# MCB-USI-WM-BN-BM-22-v1_0_0.net
KiCad netlist of a schematic drawn in EAGLE
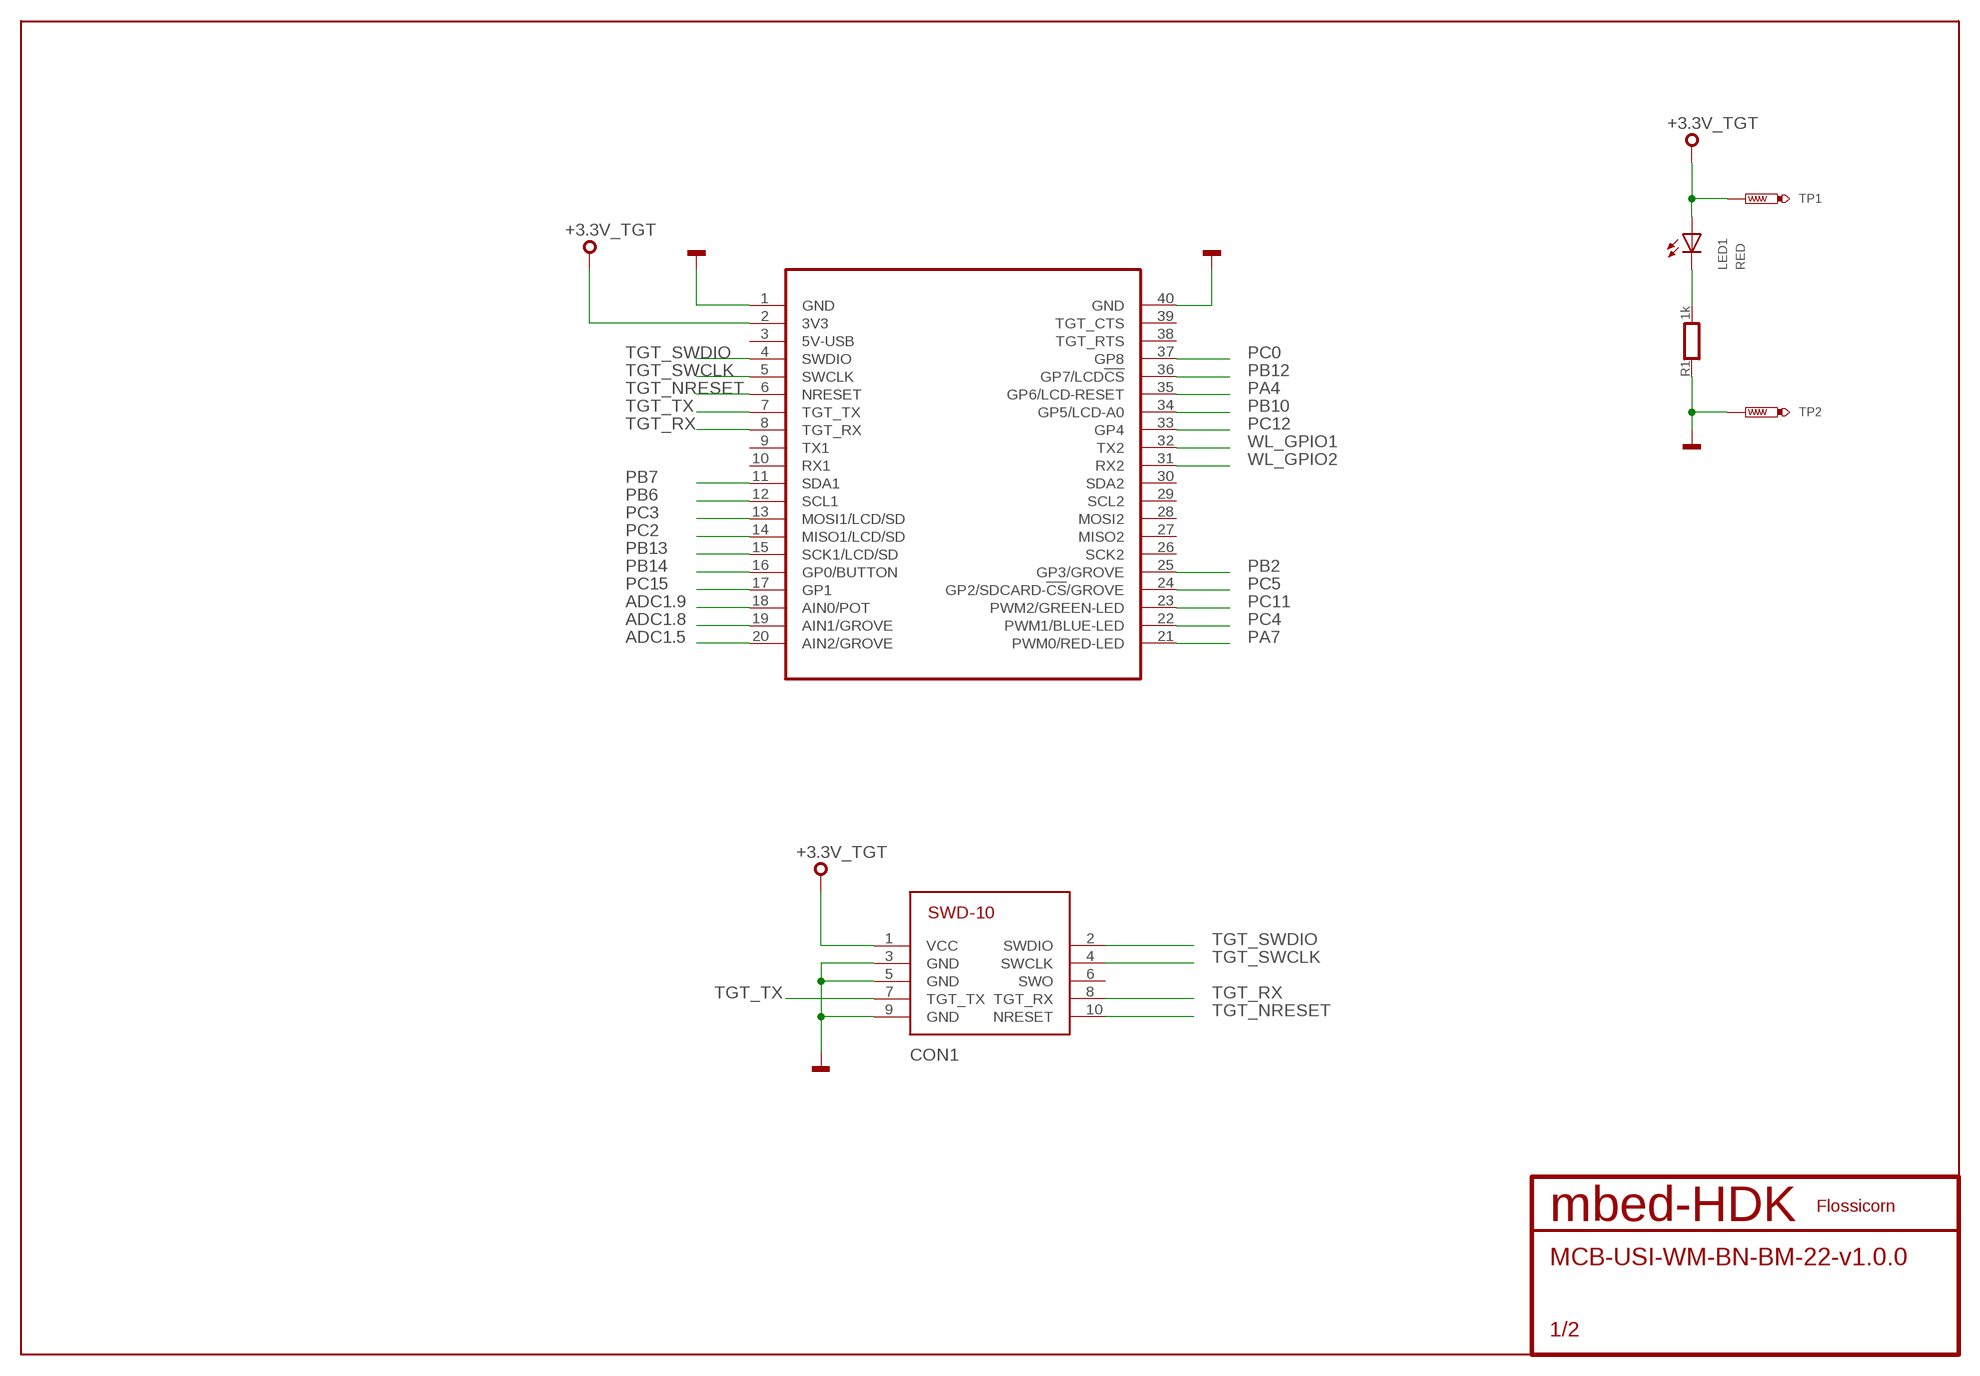
[diagram p0: schematic, sheet 1]
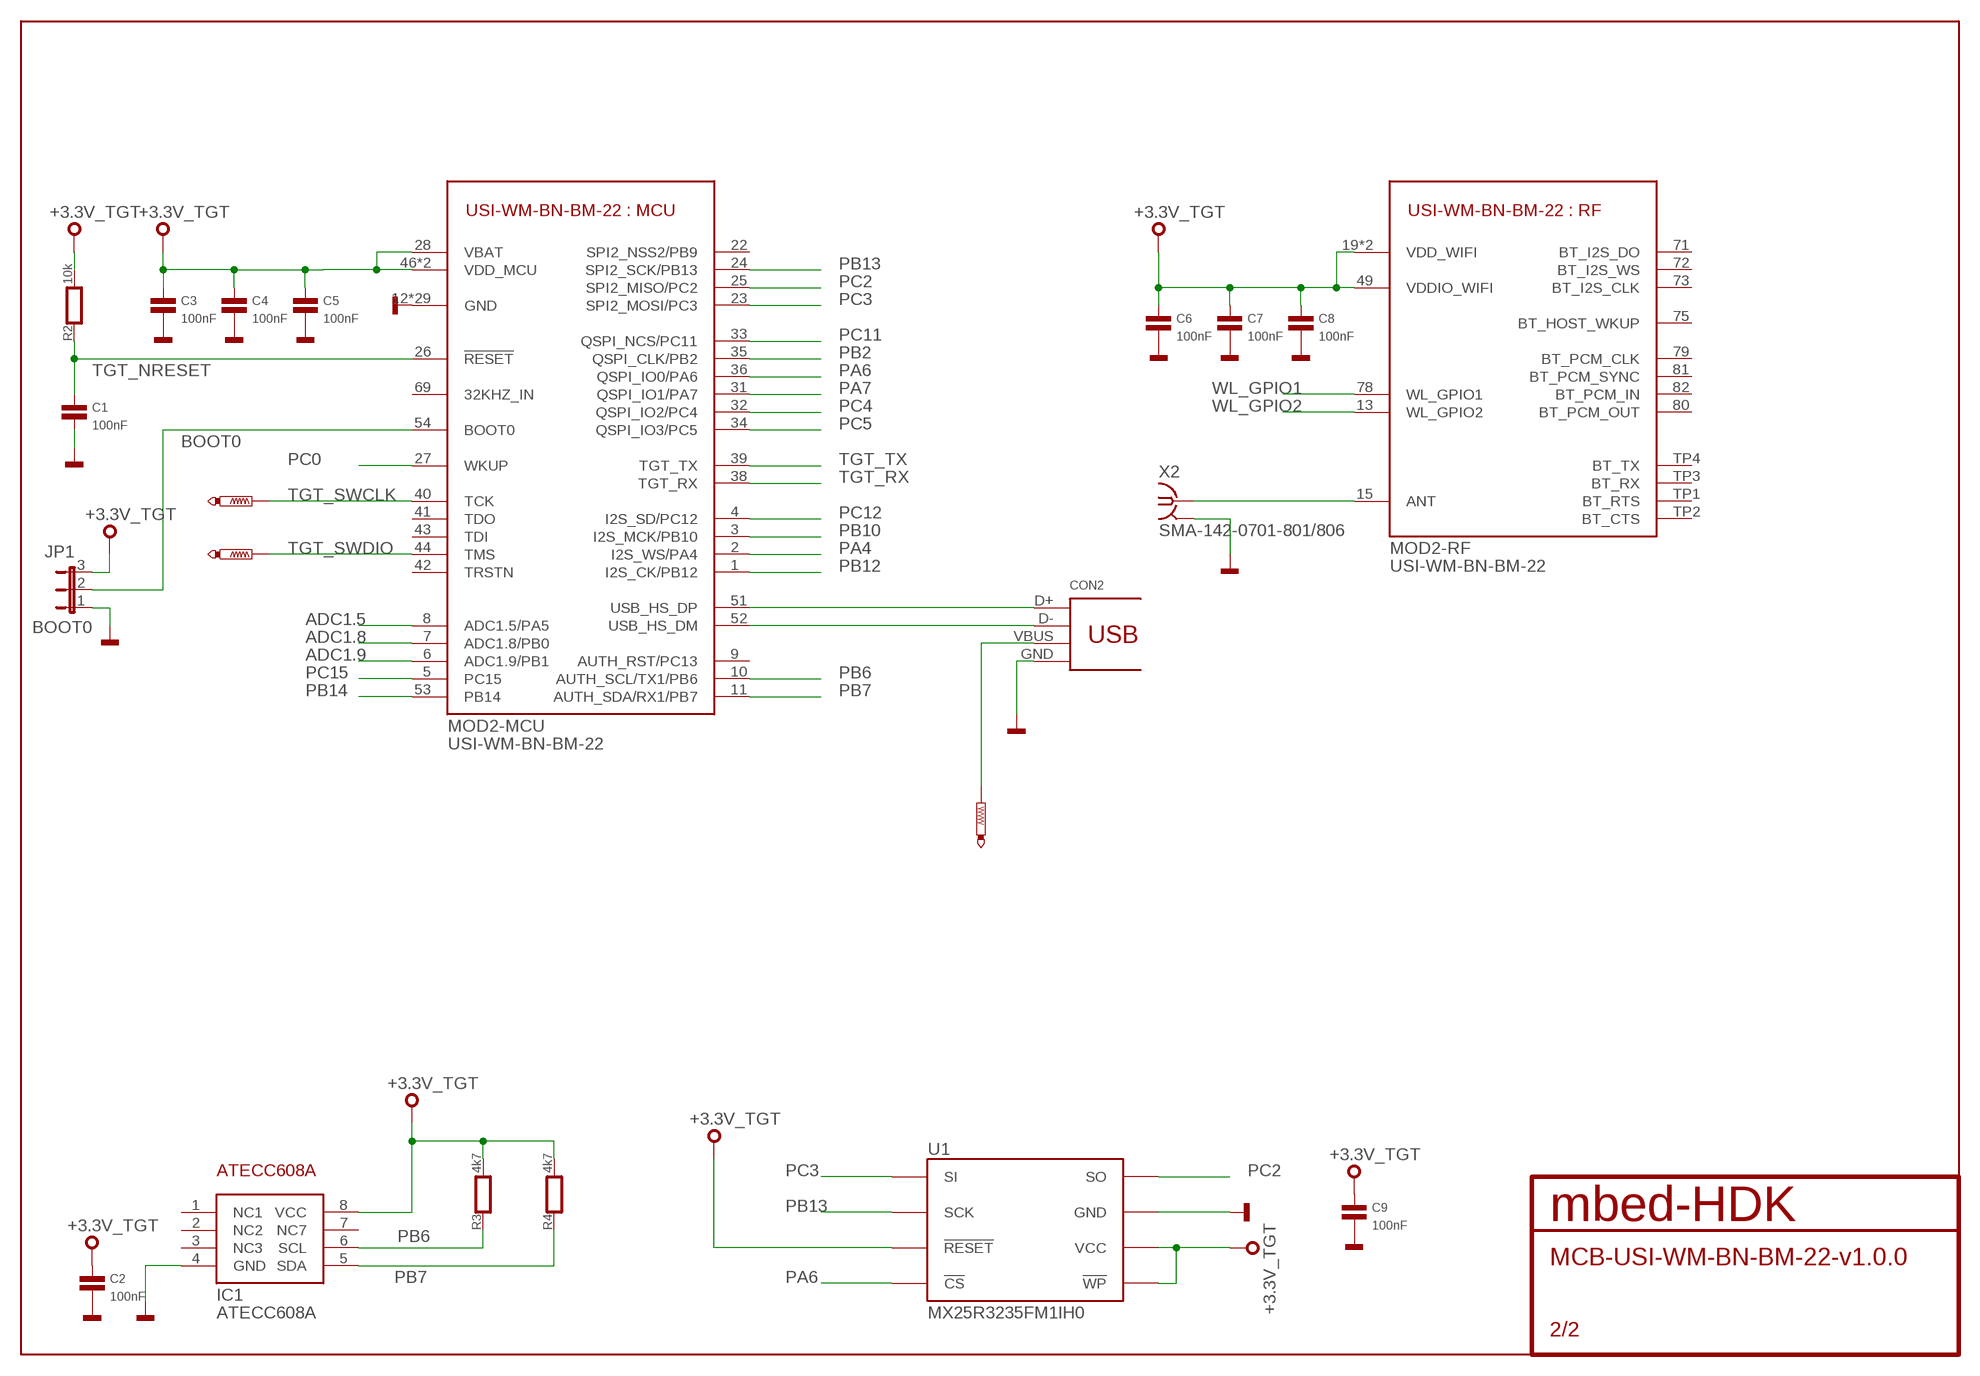
[diagram p1: schematic, sheet 2]

(export (version "E")
  (design (tool "Eeschema 10.0.6"))
  (components
    (comp (ref "CON1")
      (value "SWD-10/TC2050_SMD")
      (footprint "eagle-import:FTSH-105-02")
      (libsource (lib "eagle-import") (part "SWD-10/TC2050_SMD"))
    )
    (comp (ref "LED1")
      (value "RED")
      (footprint "eagle-import:CHIPLED_0603")
      (fields (field (name "MF") "Wurth Electronics Inc"))
      (libsource (lib "eagle-import") (part "SMD_LED0603"))
    )
    (comp (ref "MOD1")
      (value "MODULE_DAUGHTER")
      (footprint "eagle-import:MODULE_DAUGHTER")
      (libsource (lib "eagle-import") (part "MODULE_DAUGHTER"))
    )
    (comp (ref "R1")
      (value "1k")
      (footprint "eagle-import:0603")
      (libsource (lib "eagle-import") (part "RESISTOR0603"))
    )
    (comp (ref "SS1")
      (value "FLOSSICORN0.5")
      (footprint "eagle-import:FLOSSICORN-0.5")
      (libsource (lib "eagle-import") (part "FLOSSICORN0.5"))
    )
    (comp (ref "TP1")
      (value "TEST-POINT-50R-PTH")
      (footprint "eagle-import:TP50-PTH")
      (libsource (lib "eagle-import") (part "TEST-POINT-50R-PTH"))
    )
    (comp (ref "TP2")
      (value "TEST-POINT-50R-PTH")
      (footprint "eagle-import:TP50-PTH")
      (libsource (lib "eagle-import") (part "TEST-POINT-50R-PTH"))
    )
    (comp (ref "C1")
      (value "100nF")
      (footprint "eagle-import:0603")
      (libsource (lib "eagle-import") (part "CAPACITOR0603"))
    )
    (comp (ref "C2")
      (value "100nF")
      (footprint "eagle-import:0603")
      (libsource (lib "eagle-import") (part "CAPACITOR0603"))
    )
    (comp (ref "C3")
      (value "100nF")
      (footprint "eagle-import:0603")
      (libsource (lib "eagle-import") (part "CAPACITOR0603"))
    )
    (comp (ref "C4")
      (value "100nF")
      (footprint "eagle-import:0603")
      (libsource (lib "eagle-import") (part "CAPACITOR0603"))
    )
    (comp (ref "C5")
      (value "100nF")
      (footprint "eagle-import:0603")
      (libsource (lib "eagle-import") (part "CAPACITOR0603"))
    )
    (comp (ref "C6")
      (value "100nF")
      (footprint "eagle-import:0603")
      (libsource (lib "eagle-import") (part "CAPACITOR0603"))
    )
    (comp (ref "C7")
      (value "100nF")
      (footprint "eagle-import:0603")
      (libsource (lib "eagle-import") (part "CAPACITOR0603"))
    )
    (comp (ref "C8")
      (value "100nF")
      (footprint "eagle-import:0603")
      (libsource (lib "eagle-import") (part "CAPACITOR0603"))
    )
    (comp (ref "C9")
      (value "100nF")
      (footprint "eagle-import:0603")
      (libsource (lib "eagle-import") (part "CAPACITOR0603"))
    )
    (comp (ref "CON2")
      (value "47346-0001")
      (footprint "eagle-import:USB-MICRO-B-H")
      (fields (field (name "MF") "MOLEX"))
      (libsource (lib "eagle-import") (part "47346-0001"))
    )
    (comp (ref "IC1")
      (value "ATECC608A")
      (footprint "eagle-import:SO8")
      (libsource (lib "eagle-import") (part "ATECC608A"))
    )
    (comp (ref "JP1")
      (value "BOOT0")
      (footprint "eagle-import:JP2")
      (libsource (lib "eagle-import") (part "JP2E"))
    )
    (comp (ref "MOD2")
      (value "USI-WM-BN-BM-22")
      (footprint "eagle-import:USI-WM-BN-BM-22")
      (libsource (lib "eagle-import") (part "USI-WM-BN-BM-22"))
    )
    (comp (ref "R2")
      (value "10k")
      (footprint "eagle-import:0603")
      (libsource (lib "eagle-import") (part "RESISTOR0603"))
    )
    (comp (ref "R3")
      (value "4k7")
      (footprint "eagle-import:0603")
      (libsource (lib "eagle-import") (part "RESISTOR0603"))
    )
    (comp (ref "R4")
      (value "4k7")
      (footprint "eagle-import:0603")
      (libsource (lib "eagle-import") (part "RESISTOR0603"))
    )
    (comp (ref "TP3")
      (value "PTR1TP10R")
      (footprint "eagle-import:TP10R")
      (libsource (lib "eagle-import") (part "PTR1TP10R"))
    )
    (comp (ref "TP4")
      (value "PTR1TP10R")
      (footprint "eagle-import:TP10R")
      (libsource (lib "eagle-import") (part "PTR1TP10R"))
    )
    (comp (ref "TP5")
      (value "PTR1TP07R")
      (footprint "eagle-import:TP07R")
      (libsource (lib "eagle-import") (part "PTR1TP07R"))
    )
    (comp (ref "U1")
      (value "MX25R3235FM1IH0")
      (footprint "eagle-import:SO8")
      (fields (field (name "MF") "Macronix"))
      (libsource (lib "eagle-import") (part "MX25R3235FM1IH0"))
    )
    (comp (ref "X2")
      (value "SMA-142-0701-801/806")
      (footprint "eagle-import:J502-ND-142-0701-801_806")
      (fields (field (name "MF") "JOHNSON COMPONENTS") (field (name "MPN") "142-0701-801"))
      (libsource (lib "eagle-import") (part "SMA-142-0701-801/806"))
    )
  )
  (nets
    (net (code "1") (name "+3.3V_TGT") (class "Default")
      (node (ref "C2") (pin "1") (pinfunction "P$1_1") (pintype "passive"))
      (node (ref "C3") (pin "1") (pinfunction "P$1_1") (pintype "passive"))
      (node (ref "C4") (pin "1") (pinfunction "P$1_1") (pintype "passive"))
      (node (ref "C5") (pin "1") (pinfunction "P$1_1") (pintype "passive"))
      (node (ref "C6") (pin "1") (pinfunction "P$1_1") (pintype "passive"))
      (node (ref "C7") (pin "1") (pinfunction "P$1_1") (pintype "passive"))
      (node (ref "C8") (pin "1") (pinfunction "P$1_1") (pintype "passive"))
      (node (ref "C9") (pin "1") (pinfunction "P$1_1") (pintype "passive"))
      (node (ref "CON1") (pin "1") (pinfunction "VCC_1") (pintype "bidirectional"))
      (node (ref "IC1") (pin "8") (pinfunction "VCC_8") (pintype "bidirectional"))
      (node (ref "JP1") (pin "3") (pinfunction "3_3") (pintype "passive"))
      (node (ref "LED1") (pin "A") (pinfunction "A_A") (pintype "passive"))
      (node (ref "MOD1") (pin "2") (pinfunction "3V3_2") (pintype "bidirectional"))
      (node (ref "MOD2") (pin "19") (pinfunction "VDD_WIFI_19") (pintype "bidirectional"))
      (node (ref "MOD2") (pin "20") (pinfunction "VDD_WIFI_20") (pintype "bidirectional"))
      (node (ref "MOD2") (pin "28") (pinfunction "VBAT_28") (pintype "bidirectional"))
      (node (ref "MOD2") (pin "46") (pinfunction "VDD_MCU_46") (pintype "bidirectional"))
      (node (ref "MOD2") (pin "47") (pinfunction "VDD_MCU_47") (pintype "bidirectional"))
      (node (ref "MOD2") (pin "49") (pinfunction "VDDIO_WIFI_49") (pintype "bidirectional"))
      (node (ref "R2") (pin "2") (pinfunction "P$2_2") (pintype "passive"))
      (node (ref "R3") (pin "2") (pinfunction "P$2_2") (pintype "passive"))
      (node (ref "R4") (pin "2") (pinfunction "P$2_2") (pintype "passive"))
      (node (ref "TP1") (pin "TP") (pinfunction "TP_TP") (pintype "input"))
      (node (ref "U1") (pin "3") (pinfunction "~{WP}_3") (pintype "bidirectional"))
      (node (ref "U1") (pin "7") (pinfunction "~{RESET}_7") (pintype "bidirectional"))
      (node (ref "U1") (pin "8") (pinfunction "VCC_8") (pintype "bidirectional"))
    )
    (net (code "2") (name "ADC1.5") (class "Default")
      (node (ref "MOD1") (pin "20") (pinfunction "AIN2/GROVE_20") (pintype "bidirectional"))
      (node (ref "MOD2") (pin "8") (pinfunction "ADC1.5/PA5_8") (pintype "bidirectional"))
    )
    (net (code "3") (name "ADC1.8") (class "Default")
      (node (ref "MOD1") (pin "19") (pinfunction "AIN1/GROVE_19") (pintype "bidirectional"))
      (node (ref "MOD2") (pin "7") (pinfunction "ADC1.8/PB0_7") (pintype "bidirectional"))
    )
    (net (code "4") (name "ADC1.9") (class "Default")
      (node (ref "MOD1") (pin "18") (pinfunction "AIN0/POT_18") (pintype "bidirectional"))
      (node (ref "MOD2") (pin "6") (pinfunction "ADC1.9/PB1_6") (pintype "bidirectional"))
    )
    (net (code "5") (name "BOOT0") (class "Default")
      (node (ref "JP1") (pin "2") (pinfunction "2_2") (pintype "passive"))
      (node (ref "MOD2") (pin "54") (pinfunction "BOOT0_54") (pintype "bidirectional"))
    )
    (net (code "6") (name "GND") (class "Default")
      (node (ref "C1") (pin "2") (pinfunction "P$2_2") (pintype "passive"))
      (node (ref "C2") (pin "2") (pinfunction "P$2_2") (pintype "passive"))
      (node (ref "C3") (pin "2") (pinfunction "P$2_2") (pintype "passive"))
      (node (ref "C4") (pin "2") (pinfunction "P$2_2") (pintype "passive"))
      (node (ref "C5") (pin "2") (pinfunction "P$2_2") (pintype "passive"))
      (node (ref "C6") (pin "2") (pinfunction "P$2_2") (pintype "passive"))
      (node (ref "C7") (pin "2") (pinfunction "P$2_2") (pintype "passive"))
      (node (ref "C8") (pin "2") (pinfunction "P$2_2") (pintype "passive"))
      (node (ref "C9") (pin "2") (pinfunction "P$2_2") (pintype "passive"))
      (node (ref "CON1") (pin "3") (pinfunction "GND_3") (pintype "bidirectional"))
      (node (ref "CON1") (pin "5") (pinfunction "GND_5") (pintype "bidirectional"))
      (node (ref "CON1") (pin "9") (pinfunction "GND_9") (pintype "bidirectional"))
      (node (ref "CON2") (pin "GND") (pinfunction "GND_GND") (pintype "bidirectional"))
      (node (ref "IC1") (pin "4") (pinfunction "GND_4") (pintype "bidirectional"))
      (node (ref "JP1") (pin "1") (pinfunction "1_1") (pintype "passive"))
      (node (ref "MOD1") (pin "1") (pinfunction "GND_1") (pintype "bidirectional"))
      (node (ref "MOD1") (pin "40") (pinfunction "GND_40") (pintype "bidirectional"))
      (node (ref "MOD2") (pin "12") (pinfunction "GND_12") (pintype "bidirectional"))
      (node (ref "MOD2") (pin "14") (pinfunction "GND_14") (pintype "bidirectional"))
      (node (ref "MOD2") (pin "16") (pinfunction "GND_16") (pintype "bidirectional"))
      (node (ref "MOD2") (pin "17") (pinfunction "GND_17") (pintype "bidirectional"))
      (node (ref "MOD2") (pin "18") (pinfunction "GND_18") (pintype "bidirectional"))
      (node (ref "MOD2") (pin "21") (pinfunction "GND_21") (pintype "bidirectional"))
      (node (ref "MOD2") (pin "29") (pinfunction "GND_29") (pintype "bidirectional"))
      (node (ref "MOD2") (pin "30") (pinfunction "GND_30") (pintype "bidirectional"))
      (node (ref "MOD2") (pin "37") (pinfunction "GND_37") (pintype "bidirectional"))
      (node (ref "MOD2") (pin "45") (pinfunction "GND_45") (pintype "bidirectional"))
      (node (ref "MOD2") (pin "48") (pinfunction "GND_48") (pintype "bidirectional"))
      (node (ref "MOD2") (pin "50") (pinfunction "GND_50") (pintype "bidirectional"))
      (node (ref "MOD2") (pin "55") (pinfunction "GND_55") (pintype "bidirectional"))
      (node (ref "MOD2") (pin "56") (pinfunction "GND_56") (pintype "bidirectional"))
      (node (ref "MOD2") (pin "57") (pinfunction "GND_57") (pintype "bidirectional"))
      (node (ref "MOD2") (pin "58") (pinfunction "GND_58") (pintype "bidirectional"))
      (node (ref "MOD2") (pin "59") (pinfunction "GND_59") (pintype "bidirectional"))
      (node (ref "MOD2") (pin "60") (pinfunction "GND_60") (pintype "bidirectional"))
      (node (ref "MOD2") (pin "61") (pinfunction "GND_61") (pintype "bidirectional"))
      (node (ref "MOD2") (pin "62") (pinfunction "GND_62") (pintype "bidirectional"))
      (node (ref "MOD2") (pin "63") (pinfunction "GND_63") (pintype "bidirectional"))
      (node (ref "MOD2") (pin "64") (pinfunction "GND_64") (pintype "bidirectional"))
      (node (ref "MOD2") (pin "65") (pinfunction "GND_65") (pintype "bidirectional"))
      (node (ref "MOD2") (pin "66") (pinfunction "GND_66") (pintype "bidirectional"))
      (node (ref "MOD2") (pin "67") (pinfunction "GND_67") (pintype "bidirectional"))
      (node (ref "MOD2") (pin "68") (pinfunction "GND_68") (pintype "bidirectional"))
      (node (ref "MOD2") (pin "70") (pinfunction "GND_70") (pintype "bidirectional"))
      (node (ref "MOD2") (pin "74") (pinfunction "GND_74") (pintype "bidirectional"))
      (node (ref "MOD2") (pin "83") (pinfunction "GND_83") (pintype "bidirectional"))
      (node (ref "R1") (pin "1") (pinfunction "P$1_1") (pintype "passive"))
      (node (ref "TP2") (pin "TP") (pinfunction "TP_TP") (pintype "input"))
      (node (ref "U1") (pin "4") (pinfunction "GND_4") (pintype "bidirectional"))
      (node (ref "X2") (pin "G@1") (pinfunction "2_G@1") (pintype "passive"))
      (node (ref "X2") (pin "G@2") (pinfunction "2_G@2") (pintype "passive"))
      (node (ref "X2") (pin "G@3") (pinfunction "2_G@3") (pintype "passive"))
      (node (ref "X2") (pin "G@4") (pinfunction "2_G@4") (pintype "passive"))
    )
    (net (code "7") (name "Net-(CON2-PadVBUS)") (class "Default")
      (node (ref "CON2") (pin "VBUS") (pinfunction "VBUS_VBUS") (pintype "bidirectional"))
      (node (ref "TP5") (pin "TP") (pinfunction "TP_TP") (pintype "input"))
    )
    (net (code "8") (name "Net-(MOD2A-USB_HS_DM)") (class "Default")
      (node (ref "CON2") (pin "D-") (pinfunction "D-_D-") (pintype "bidirectional"))
      (node (ref "MOD2") (pin "52") (pinfunction "USB_HS_DM_52") (pintype "bidirectional"))
    )
    (net (code "9") (name "Net-(MOD2A-USB_HS_DP)") (class "Default")
      (node (ref "CON2") (pin "D+") (pinfunction "D+_D+") (pintype "bidirectional"))
      (node (ref "MOD2") (pin "51") (pinfunction "USB_HS_DP_51") (pintype "bidirectional"))
    )
    (net (code "10") (name "Net-(MOD2B-ANT)") (class "Default")
      (node (ref "MOD2") (pin "15") (pinfunction "ANT_15") (pintype "bidirectional"))
      (node (ref "X2") (pin "1") (pinfunction "1_1") (pintype "passive"))
    )
    (net (code "11") (name "Net-(R1-P$2)") (class "Default")
      (node (ref "LED1") (pin "C") (pinfunction "C_C") (pintype "passive"))
      (node (ref "R1") (pin "2") (pinfunction "P$2_2") (pintype "passive"))
    )
    (net (code "12") (name "PA4") (class "Default")
      (node (ref "MOD1") (pin "35") (pinfunction "GP6/LCD-RESET_35") (pintype "bidirectional"))
      (node (ref "MOD2") (pin "2") (pinfunction "I2S_WS/PA4_2") (pintype "bidirectional"))
    )
    (net (code "13") (name "PA6") (class "Default")
      (node (ref "MOD2") (pin "36") (pinfunction "QSPI_IO0/PA6_36") (pintype "bidirectional"))
      (node (ref "U1") (pin "1") (pinfunction "~{CS}_1") (pintype "bidirectional"))
    )
    (net (code "14") (name "PA7") (class "Default")
      (node (ref "MOD1") (pin "21") (pinfunction "PWM0/RED-LED_21") (pintype "bidirectional"))
      (node (ref "MOD2") (pin "31") (pinfunction "QSPI_IO1/PA7_31") (pintype "bidirectional"))
    )
    (net (code "15") (name "PB2") (class "Default")
      (node (ref "MOD1") (pin "25") (pinfunction "GP3/GROVE_25") (pintype "bidirectional"))
      (node (ref "MOD2") (pin "35") (pinfunction "QSPI_CLK/PB2_35") (pintype "bidirectional"))
    )
    (net (code "16") (name "PB6") (class "Default")
      (node (ref "IC1") (pin "6") (pinfunction "SCL_6") (pintype "bidirectional"))
      (node (ref "MOD1") (pin "12") (pinfunction "SCL1_12") (pintype "bidirectional"))
      (node (ref "MOD2") (pin "10") (pinfunction "AUTH_SCL/TX1/PB6_10") (pintype "bidirectional"))
      (node (ref "R3") (pin "1") (pinfunction "P$1_1") (pintype "passive"))
    )
    (net (code "17") (name "PB7") (class "Default")
      (node (ref "IC1") (pin "5") (pinfunction "SDA_5") (pintype "bidirectional"))
      (node (ref "MOD1") (pin "11") (pinfunction "SDA1_11") (pintype "bidirectional"))
      (node (ref "MOD2") (pin "11") (pinfunction "AUTH_SDA/RX1/PB7_11") (pintype "bidirectional"))
      (node (ref "R4") (pin "1") (pinfunction "P$1_1") (pintype "passive"))
    )
    (net (code "18") (name "PB10") (class "Default")
      (node (ref "MOD1") (pin "34") (pinfunction "GP5/LCD-A0_34") (pintype "bidirectional"))
      (node (ref "MOD2") (pin "3") (pinfunction "I2S_MCK/PB10_3") (pintype "bidirectional"))
    )
    (net (code "19") (name "PB12") (class "Default")
      (node (ref "MOD1") (pin "36") (pinfunction "GP7/LCD~{CS}_36") (pintype "bidirectional"))
      (node (ref "MOD2") (pin "1") (pinfunction "I2S_CK/PB12_1") (pintype "bidirectional"))
    )
    (net (code "20") (name "PB13") (class "Default")
      (node (ref "MOD1") (pin "15") (pinfunction "SCK1/LCD/SD_15") (pintype "bidirectional"))
      (node (ref "MOD2") (pin "24") (pinfunction "SPI2_SCK/PB13_24") (pintype "bidirectional"))
      (node (ref "U1") (pin "6") (pinfunction "SCK_6") (pintype "bidirectional"))
    )
    (net (code "21") (name "PB14") (class "Default")
      (node (ref "MOD1") (pin "16") (pinfunction "GP0/BUTTON_16") (pintype "bidirectional"))
      (node (ref "MOD2") (pin "53") (pinfunction "PB14_53") (pintype "bidirectional"))
    )
    (net (code "22") (name "PC0") (class "Default")
      (node (ref "MOD1") (pin "37") (pinfunction "GP8_37") (pintype "bidirectional"))
      (node (ref "MOD2") (pin "27") (pinfunction "WKUP_27") (pintype "bidirectional"))
    )
    (net (code "23") (name "PC2") (class "Default")
      (node (ref "MOD1") (pin "14") (pinfunction "MISO1/LCD/SD_14") (pintype "bidirectional"))
      (node (ref "MOD2") (pin "25") (pinfunction "SPI2_MISO/PC2_25") (pintype "bidirectional"))
      (node (ref "U1") (pin "2") (pinfunction "SO_2") (pintype "bidirectional"))
    )
    (net (code "24") (name "PC3") (class "Default")
      (node (ref "MOD1") (pin "13") (pinfunction "MOSI1/LCD/SD_13") (pintype "bidirectional"))
      (node (ref "MOD2") (pin "23") (pinfunction "SPI2_MOSI/PC3_23") (pintype "bidirectional"))
      (node (ref "U1") (pin "5") (pinfunction "SI_5") (pintype "bidirectional"))
    )
    (net (code "25") (name "PC4") (class "Default")
      (node (ref "MOD1") (pin "22") (pinfunction "PWM1/BLUE-LED_22") (pintype "bidirectional"))
      (node (ref "MOD2") (pin "32") (pinfunction "QSPI_IO2/PC4_32") (pintype "bidirectional"))
    )
    (net (code "26") (name "PC5") (class "Default")
      (node (ref "MOD1") (pin "24") (pinfunction "GP2/SDCARD-~{CS}/GROVE_24") (pintype "bidirectional"))
      (node (ref "MOD2") (pin "34") (pinfunction "QSPI_IO3/PC5_34") (pintype "bidirectional"))
    )
    (net (code "27") (name "PC11") (class "Default")
      (node (ref "MOD1") (pin "23") (pinfunction "PWM2/GREEN-LED_23") (pintype "bidirectional"))
      (node (ref "MOD2") (pin "33") (pinfunction "QSPI_NCS/PC11_33") (pintype "bidirectional"))
    )
    (net (code "28") (name "PC12") (class "Default")
      (node (ref "MOD1") (pin "33") (pinfunction "GP4_33") (pintype "bidirectional"))
      (node (ref "MOD2") (pin "4") (pinfunction "I2S_SD/PC12_4") (pintype "bidirectional"))
    )
    (net (code "29") (name "PC15") (class "Default")
      (node (ref "MOD1") (pin "17") (pinfunction "GP1_17") (pintype "bidirectional"))
      (node (ref "MOD2") (pin "5") (pinfunction "PC15_5") (pintype "bidirectional"))
    )
    (net (code "30") (name "TGT_NRESET") (class "Default")
      (node (ref "C1") (pin "1") (pinfunction "P$1_1") (pintype "passive"))
      (node (ref "CON1") (pin "10") (pinfunction "NRESET_10") (pintype "bidirectional"))
      (node (ref "MOD1") (pin "6") (pinfunction "NRESET_6") (pintype "bidirectional"))
      (node (ref "MOD2") (pin "26") (pinfunction "~{RESET}_26") (pintype "bidirectional"))
      (node (ref "R2") (pin "1") (pinfunction "P$1_1") (pintype "passive"))
    )
    (net (code "31") (name "TGT_RX") (class "Default")
      (node (ref "CON1") (pin "8") (pinfunction "TGT_RX_8") (pintype "bidirectional"))
      (node (ref "MOD1") (pin "8") (pinfunction "TGT_RX_8") (pintype "bidirectional"))
      (node (ref "MOD2") (pin "38") (pinfunction "TGT_RX_38") (pintype "bidirectional"))
    )
    (net (code "32") (name "TGT_SWCLK") (class "Default")
      (node (ref "CON1") (pin "4") (pinfunction "SWCLK_4") (pintype "bidirectional"))
      (node (ref "MOD1") (pin "5") (pinfunction "SWCLK_5") (pintype "bidirectional"))
      (node (ref "MOD2") (pin "40") (pinfunction "TCK_40") (pintype "bidirectional"))
      (node (ref "TP4") (pin "TP") (pinfunction "TP_TP") (pintype "input"))
    )
    (net (code "33") (name "TGT_SWDIO") (class "Default")
      (node (ref "CON1") (pin "2") (pinfunction "SWDIO_2") (pintype "bidirectional"))
      (node (ref "MOD1") (pin "4") (pinfunction "SWDIO_4") (pintype "bidirectional"))
      (node (ref "MOD2") (pin "44") (pinfunction "TMS_44") (pintype "bidirectional"))
      (node (ref "TP3") (pin "TP") (pinfunction "TP_TP") (pintype "input"))
    )
    (net (code "34") (name "TGT_TX") (class "Default")
      (node (ref "CON1") (pin "7") (pinfunction "TGT_TX_7") (pintype "bidirectional"))
      (node (ref "MOD1") (pin "7") (pinfunction "TGT_TX_7") (pintype "bidirectional"))
      (node (ref "MOD2") (pin "39") (pinfunction "TGT_TX_39") (pintype "bidirectional"))
    )
    (net (code "35") (name "WL_GPIO1") (class "Default")
      (node (ref "MOD1") (pin "32") (pinfunction "TX2_32") (pintype "bidirectional"))
      (node (ref "MOD2") (pin "78") (pinfunction "WL_GPIO1_78") (pintype "bidirectional"))
    )
    (net (code "36") (name "WL_GPIO2") (class "Default")
      (node (ref "MOD1") (pin "31") (pinfunction "RX2_31") (pintype "bidirectional"))
      (node (ref "MOD2") (pin "13") (pinfunction "WL_GPIO2_13") (pintype "bidirectional"))
    )
    (net (code "37") (name "unconnected-(CON1-SWO-Pad6)") (class "Default")
      (node (ref "CON1") (pin "6") (pinfunction "SWO_6") (pintype "bidirectional"))
    )
    (net (code "38") (name "unconnected-(IC1-NC1-Pad1)") (class "Default")
      (node (ref "IC1") (pin "1") (pinfunction "NC1_1") (pintype "bidirectional"))
    )
    (net (code "39") (name "unconnected-(IC1-NC2-Pad2)") (class "Default")
      (node (ref "IC1") (pin "2") (pinfunction "NC2_2") (pintype "bidirectional"))
    )
    (net (code "40") (name "unconnected-(IC1-NC3-Pad3)") (class "Default")
      (node (ref "IC1") (pin "3") (pinfunction "NC3_3") (pintype "bidirectional"))
    )
    (net (code "41") (name "unconnected-(IC1-NC7-Pad7)") (class "Default")
      (node (ref "IC1") (pin "7") (pinfunction "NC7_7") (pintype "bidirectional"))
    )
    (net (code "42") (name "unconnected-(MOD1-5V-USB-Pad3)") (class "Default")
      (node (ref "MOD1") (pin "3") (pinfunction "5V-USB_3") (pintype "bidirectional"))
    )
    (net (code "43") (name "unconnected-(MOD1-MISO2-Pad27)") (class "Default")
      (node (ref "MOD1") (pin "27") (pinfunction "MISO2_27") (pintype "bidirectional"))
    )
    (net (code "44") (name "unconnected-(MOD1-MOSI2-Pad28)") (class "Default")
      (node (ref "MOD1") (pin "28") (pinfunction "MOSI2_28") (pintype "bidirectional"))
    )
    (net (code "45") (name "unconnected-(MOD1-RX1-Pad10)") (class "Default")
      (node (ref "MOD1") (pin "10") (pinfunction "RX1_10") (pintype "bidirectional"))
    )
    (net (code "46") (name "unconnected-(MOD1-SCK2-Pad26)") (class "Default")
      (node (ref "MOD1") (pin "26") (pinfunction "SCK2_26") (pintype "bidirectional"))
    )
    (net (code "47") (name "unconnected-(MOD1-SCL2-Pad29)") (class "Default")
      (node (ref "MOD1") (pin "29") (pinfunction "SCL2_29") (pintype "bidirectional"))
    )
    (net (code "48") (name "unconnected-(MOD1-SDA2-Pad30)") (class "Default")
      (node (ref "MOD1") (pin "30") (pinfunction "SDA2_30") (pintype "bidirectional"))
    )
    (net (code "49") (name "unconnected-(MOD1-TGT_CTS-Pad39)") (class "Default")
      (node (ref "MOD1") (pin "39") (pinfunction "TGT_CTS_39") (pintype "bidirectional"))
    )
    (net (code "50") (name "unconnected-(MOD1-TGT_RTS-Pad38)") (class "Default")
      (node (ref "MOD1") (pin "38") (pinfunction "TGT_RTS_38") (pintype "bidirectional"))
    )
    (net (code "51") (name "unconnected-(MOD1-TX1-Pad9)") (class "Default")
      (node (ref "MOD1") (pin "9") (pinfunction "TX1_9") (pintype "bidirectional"))
    )
    (net (code "52") (name "unconnected-(MOD2A-32KHZ_IN-Pad69)") (class "Default")
      (node (ref "MOD2") (pin "69") (pinfunction "32KHZ_IN_69") (pintype "bidirectional"))
    )
    (net (code "53") (name "unconnected-(MOD2A-AUTH_RST{slash}PC13-Pad9)") (class "Default")
      (node (ref "MOD2") (pin "9") (pinfunction "AUTH_RST/PC13_9") (pintype "bidirectional"))
    )
    (net (code "54") (name "unconnected-(MOD2A-SPI2_NSS2{slash}PB9-Pad22)") (class "Default")
      (node (ref "MOD2") (pin "22") (pinfunction "SPI2_NSS2/PB9_22") (pintype "bidirectional"))
    )
    (net (code "55") (name "unconnected-(MOD2A-TDI-Pad43)") (class "Default")
      (node (ref "MOD2") (pin "43") (pinfunction "TDI_43") (pintype "bidirectional"))
    )
    (net (code "56") (name "unconnected-(MOD2A-TDO-Pad41)") (class "Default")
      (node (ref "MOD2") (pin "41") (pinfunction "TDO_41") (pintype "bidirectional"))
    )
    (net (code "57") (name "unconnected-(MOD2A-TRSTN-Pad42)") (class "Default")
      (node (ref "MOD2") (pin "42") (pinfunction "TRSTN_42") (pintype "bidirectional"))
    )
    (net (code "58") (name "unconnected-(MOD2B-BT_CTS-PadTP2)") (class "Default")
      (node (ref "MOD2") (pin "TP2") (pinfunction "BT_CTS_TP2") (pintype "bidirectional"))
    )
    (net (code "59") (name "unconnected-(MOD2B-BT_HOST_WKUP-Pad75)") (class "Default")
      (node (ref "MOD2") (pin "75") (pinfunction "BT_HOST_WKUP_75") (pintype "bidirectional"))
    )
    (net (code "60") (name "unconnected-(MOD2B-BT_I2S_CLK-Pad73)") (class "Default")
      (node (ref "MOD2") (pin "73") (pinfunction "BT_I2S_CLK_73") (pintype "bidirectional"))
    )
    (net (code "61") (name "unconnected-(MOD2B-BT_I2S_DO-Pad71)") (class "Default")
      (node (ref "MOD2") (pin "71") (pinfunction "BT_I2S_DO_71") (pintype "bidirectional"))
    )
    (net (code "62") (name "unconnected-(MOD2B-BT_I2S_WS-Pad72)") (class "Default")
      (node (ref "MOD2") (pin "72") (pinfunction "BT_I2S_WS_72") (pintype "bidirectional"))
    )
    (net (code "63") (name "unconnected-(MOD2B-BT_PCM_CLK-Pad79)") (class "Default")
      (node (ref "MOD2") (pin "79") (pinfunction "BT_PCM_CLK_79") (pintype "bidirectional"))
    )
    (net (code "64") (name "unconnected-(MOD2B-BT_PCM_IN-Pad82)") (class "Default")
      (node (ref "MOD2") (pin "82") (pinfunction "BT_PCM_IN_82") (pintype "bidirectional"))
    )
    (net (code "65") (name "unconnected-(MOD2B-BT_PCM_OUT-Pad80)") (class "Default")
      (node (ref "MOD2") (pin "80") (pinfunction "BT_PCM_OUT_80") (pintype "bidirectional"))
    )
    (net (code "66") (name "unconnected-(MOD2B-BT_PCM_SYNC-Pad81)") (class "Default")
      (node (ref "MOD2") (pin "81") (pinfunction "BT_PCM_SYNC_81") (pintype "bidirectional"))
    )
    (net (code "67") (name "unconnected-(MOD2B-BT_RTS-PadTP1)") (class "Default")
      (node (ref "MOD2") (pin "TP1") (pinfunction "BT_RTS_TP1") (pintype "bidirectional"))
    )
    (net (code "68") (name "unconnected-(MOD2B-BT_RX-PadTP3)") (class "Default")
      (node (ref "MOD2") (pin "TP3") (pinfunction "BT_RX_TP3") (pintype "bidirectional"))
    )
    (net (code "69") (name "unconnected-(MOD2B-BT_TX-PadTP4)") (class "Default")
      (node (ref "MOD2") (pin "TP4") (pinfunction "BT_TX_TP4") (pintype "bidirectional"))
    )
  )
)
